# signal_processing_module.net
KiCad netlist of a schematic drawn in EAGLE
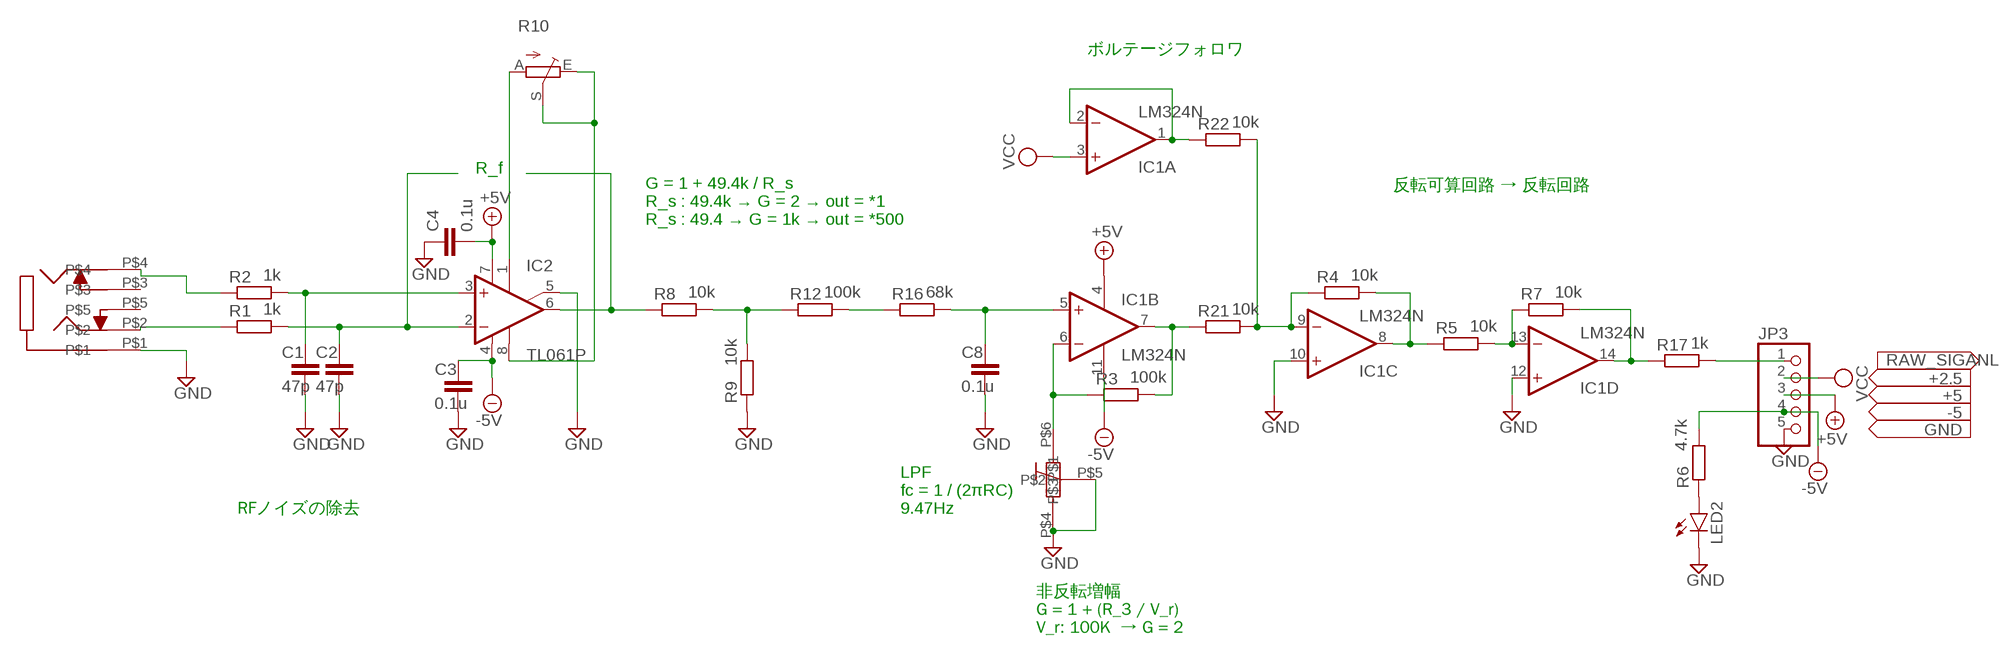
[diagram p0: schematic, sheet 1]

(export (version "E")
  (design (tool "Eeschema 10.0.6"))
  (components
    (comp (ref "C1")
      (value "47p")
      (footprint "eagle-import:C025-024X044")
      (libsource (lib "eagle-import") (part "C-EU025-024X044"))
    )
    (comp (ref "C2")
      (value "47p")
      (footprint "eagle-import:C025-024X044")
      (libsource (lib "eagle-import") (part "C-EU025-024X044"))
    )
    (comp (ref "C3")
      (value "0.1u")
      (footprint "eagle-import:C025-024X044")
      (libsource (lib "eagle-import") (part "C-EU025-024X044"))
    )
    (comp (ref "C4")
      (value "0.1u")
      (footprint "eagle-import:C025-024X044")
      (libsource (lib "eagle-import") (part "C-EU025-024X044"))
    )
    (comp (ref "C8")
      (value "0.1u")
      (footprint "eagle-import:C025-024X044")
      (libsource (lib "eagle-import") (part "C-EU025-024X044"))
    )
    (comp (ref "IC1")
      (value "LM324N")
      (footprint "eagle-import:DIL14")
      (libsource (lib "eagle-import") (part "LM324N"))
    )
    (comp (ref "IC2")
      (value "TL061P")
      (footprint "eagle-import:DIL08")
      (libsource (lib "eagle-import") (part "TL061P"))
    )
    (comp (ref "JP3")
      (value "PINHD-1X5")
      (footprint "eagle-import:1X05")
      (libsource (lib "eagle-import") (part "PINHD-1X5"))
    )
    (comp (ref "LED2")
      (value "LED3MM")
      (footprint "eagle-import:LED3MM")
      (libsource (lib "eagle-import") (part "LED3MM"))
    )
    (comp (ref "R1")
      (value "1k")
      (footprint "eagle-import:0204_7")
      (libsource (lib "eagle-import") (part "R-EU_0204/7"))
    )
    (comp (ref "R2")
      (value "1k")
      (footprint "eagle-import:0204_7")
      (libsource (lib "eagle-import") (part "R-EU_0204/7"))
    )
    (comp (ref "R3")
      (value "100k")
      (footprint "eagle-import:0204_7")
      (libsource (lib "eagle-import") (part "R-EU_0204/7"))
    )
    (comp (ref "R4")
      (value "10k")
      (footprint "eagle-import:0204_7")
      (libsource (lib "eagle-import") (part "R-EU_0204/7"))
    )
    (comp (ref "R5")
      (value "10k")
      (footprint "eagle-import:0204_7")
      (libsource (lib "eagle-import") (part "R-EU_0204/7"))
    )
    (comp (ref "R6")
      (value "4.7k")
      (footprint "eagle-import:0204_7")
      (libsource (lib "eagle-import") (part "R-EU_0204/7"))
    )
    (comp (ref "R7")
      (value "10k")
      (footprint "eagle-import:0204_7")
      (libsource (lib "eagle-import") (part "R-EU_0204/7"))
    )
    (comp (ref "R8")
      (value "10k")
      (footprint "eagle-import:0204_7")
      (libsource (lib "eagle-import") (part "R-EU_0204/7"))
    )
    (comp (ref "R9")
      (value "10k")
      (footprint "eagle-import:0204_7")
      (libsource (lib "eagle-import") (part "R-EU_0204/7"))
    )
    (comp (ref "R10")
      (value "TRIM_EU-RS3")
      (footprint "eagle-import:RS3")
      (libsource (lib "eagle-import") (part "TRIM_EU-RS3"))
    )
    (comp (ref "R12")
      (value "100k")
      (footprint "eagle-import:0204_7")
      (libsource (lib "eagle-import") (part "R-EU_0204/7"))
    )
    (comp (ref "R16")
      (value "68k")
      (footprint "eagle-import:0204_7")
      (libsource (lib "eagle-import") (part "R-EU_0204/7"))
    )
    (comp (ref "R17")
      (value "1k")
      (footprint "eagle-import:0204_7")
      (libsource (lib "eagle-import") (part "R-EU_0204/7"))
    )
    (comp (ref "R21")
      (value "10k")
      (footprint "eagle-import:0204_7")
      (libsource (lib "eagle-import") (part "R-EU_0204/7"))
    )
    (comp (ref "R22")
      (value "10k")
      (footprint "eagle-import:0204_7")
      (libsource (lib "eagle-import") (part "R-EU_0204/7"))
    )
    (comp (ref "U$2")
      (value "MJ-354W-SG")
      (footprint "eagle-import:MJ-354W-SG")
      (libsource (lib "eagle-import") (part "MJ-354W-SG"))
    )
    (comp (ref "U$3")
      (value "VR_2CH")
      (footprint "eagle-import:2CH_VR")
      (libsource (lib "eagle-import") (part "VR_2CH"))
    )
  )
  (nets
    (net (code "1") (name "+5V") (class "Default")
      (node (ref "C4") (pin "2") (pinfunction "2_2") (pintype "passive"))
      (node (ref "IC1") (pin "4") (pinfunction "V+_4") (pintype "power_in"))
      (node (ref "IC2") (pin "7") (pinfunction "V+_7") (pintype "power_in"))
      (node (ref "JP3") (pin "3") (pinfunction "3_3") (pintype "passive"))
    )
    (net (code "2") (name "-5V") (class "Default")
      (node (ref "C3") (pin "1") (pinfunction "1_1") (pintype "passive"))
      (node (ref "IC1") (pin "11") (pinfunction "V-_11") (pintype "power_in"))
      (node (ref "IC2") (pin "4") (pinfunction "V-_4") (pintype "power_in"))
      (node (ref "JP3") (pin "4") (pinfunction "4_4") (pintype "passive"))
      (node (ref "R6") (pin "2") (pinfunction "2_2") (pintype "passive"))
    )
    (net (code "3") (name "GND") (class "Default")
      (node (ref "C1") (pin "2") (pinfunction "2_2") (pintype "passive"))
      (node (ref "C2") (pin "2") (pinfunction "2_2") (pintype "passive"))
      (node (ref "C3") (pin "2") (pinfunction "2_2") (pintype "passive"))
      (node (ref "C4") (pin "1") (pinfunction "1_1") (pintype "passive"))
      (node (ref "C8") (pin "2") (pinfunction "2_2") (pintype "passive"))
      (node (ref "IC1") (pin "10") (pinfunction "+IN_10") (pintype "input"))
      (node (ref "IC1") (pin "12") (pinfunction "+IN_12") (pintype "input"))
      (node (ref "IC2") (pin "5") (pinfunction "ON2_5") (pintype "passive"))
      (node (ref "JP3") (pin "5") (pinfunction "5_5") (pintype "passive"))
      (node (ref "LED2") (pin "K") (pinfunction "C_K") (pintype "passive"))
      (node (ref "R9") (pin "1") (pinfunction "1_1") (pintype "passive"))
      (node (ref "U$2") (pin "P$1") (pinfunction "P$1_P$1") (pintype "bidirectional"))
      (node (ref "U$3") (pin "P$4") (pinfunction "P$1_P$4") (pintype "bidirectional"))
      (node (ref "U$3") (pin "P$5") (pinfunction "P$2_P$5") (pintype "bidirectional"))
    )
    (net (code "4") (name "Net-(IC1A--IN)") (class "Default")
      (node (ref "IC1") (pin "1") (pinfunction "OUT_1") (pintype "output"))
      (node (ref "IC1") (pin "2") (pinfunction "-IN_2") (pintype "input"))
      (node (ref "R22") (pin "1") (pinfunction "1_1") (pintype "passive"))
    )
    (net (code "5") (name "Net-(IC1B-+IN)") (class "Default")
      (node (ref "C8") (pin "1") (pinfunction "1_1") (pintype "passive"))
      (node (ref "IC1") (pin "5") (pinfunction "+IN_5") (pintype "input"))
      (node (ref "R16") (pin "2") (pinfunction "2_2") (pintype "passive"))
    )
    (net (code "6") (name "Net-(IC1B--IN)") (class "Default")
      (node (ref "IC1") (pin "6") (pinfunction "-IN_6") (pintype "input"))
      (node (ref "R3") (pin "1") (pinfunction "1_1") (pintype "passive"))
      (node (ref "U$3") (pin "P$6") (pinfunction "P$3_P$6") (pintype "bidirectional"))
    )
    (net (code "7") (name "Net-(IC1B-OUT)") (class "Default")
      (node (ref "IC1") (pin "7") (pinfunction "OUT_7") (pintype "output"))
      (node (ref "R21") (pin "1") (pinfunction "1_1") (pintype "passive"))
      (node (ref "R3") (pin "2") (pinfunction "2_2") (pintype "passive"))
    )
    (net (code "8") (name "Net-(IC1C--IN)") (class "Default")
      (node (ref "IC1") (pin "9") (pinfunction "-IN_9") (pintype "input"))
      (node (ref "R21") (pin "2") (pinfunction "2_2") (pintype "passive"))
      (node (ref "R22") (pin "2") (pinfunction "2_2") (pintype "passive"))
      (node (ref "R4") (pin "1") (pinfunction "1_1") (pintype "passive"))
    )
    (net (code "9") (name "Net-(IC1C-OUT)") (class "Default")
      (node (ref "IC1") (pin "8") (pinfunction "OUT_8") (pintype "output"))
      (node (ref "R4") (pin "2") (pinfunction "2_2") (pintype "passive"))
      (node (ref "R5") (pin "1") (pinfunction "1_1") (pintype "passive"))
    )
    (net (code "10") (name "Net-(IC1D--IN)") (class "Default")
      (node (ref "IC1") (pin "13") (pinfunction "-IN_13") (pintype "input"))
      (node (ref "R5") (pin "2") (pinfunction "2_2") (pintype "passive"))
      (node (ref "R7") (pin "1") (pinfunction "1_1") (pintype "passive"))
    )
    (net (code "11") (name "Net-(IC1D-OUT)") (class "Default")
      (node (ref "IC1") (pin "14") (pinfunction "OUT_14") (pintype "output"))
      (node (ref "R17") (pin "1") (pinfunction "1_1") (pintype "passive"))
      (node (ref "R7") (pin "2") (pinfunction "2_2") (pintype "passive"))
    )
    (net (code "12") (name "Net-(IC2-+IN)") (class "Default")
      (node (ref "C1") (pin "1") (pinfunction "1_1") (pintype "passive"))
      (node (ref "IC2") (pin "3") (pinfunction "+IN_3") (pintype "input"))
      (node (ref "R2") (pin "2") (pinfunction "2_2") (pintype "passive"))
    )
    (net (code "13") (name "Net-(IC2--IN)") (class "Default")
      (node (ref "C2") (pin "1") (pinfunction "1_1") (pintype "passive"))
      (node (ref "IC2") (pin "2") (pinfunction "-IN_2") (pintype "input"))
      (node (ref "R1") (pin "2") (pinfunction "2_2") (pintype "passive"))
    )
    (net (code "14") (name "Net-(IC2-ON1)") (class "Default")
      (node (ref "IC2") (pin "1") (pinfunction "ON1_1") (pintype "passive"))
      (node (ref "R10") (pin "A") (pinfunction "A_A") (pintype "passive"))
    )
    (net (code "15") (name "Net-(IC2-OPT)") (class "Default")
      (node (ref "IC2") (pin "8") (pinfunction "OPT_8") (pintype "passive"))
      (node (ref "R10") (pin "E") (pinfunction "E_E") (pintype "passive"))
      (node (ref "R10") (pin "S") (pinfunction "S_S") (pintype "passive"))
    )
    (net (code "16") (name "Net-(IC2-OUT)") (class "Default")
      (node (ref "IC2") (pin "6") (pinfunction "OUT_6") (pintype "output"))
      (node (ref "R8") (pin "1") (pinfunction "1_1") (pintype "passive"))
    )
    (net (code "17") (name "Net-(JP3-Pad1)") (class "Default")
      (node (ref "JP3") (pin "1") (pinfunction "1_1") (pintype "passive"))
      (node (ref "R17") (pin "2") (pinfunction "2_2") (pintype "passive"))
    )
    (net (code "18") (name "Net-(LED2-PadA)") (class "Default")
      (node (ref "LED2") (pin "A") (pinfunction "A_A") (pintype "passive"))
      (node (ref "R6") (pin "1") (pinfunction "1_1") (pintype "passive"))
    )
    (net (code "19") (name "Net-(R1-Pad1)") (class "Default")
      (node (ref "R1") (pin "1") (pinfunction "1_1") (pintype "passive"))
      (node (ref "U$2") (pin "P$2") (pinfunction "P$2_P$2") (pintype "bidirectional"))
    )
    (net (code "20") (name "Net-(R2-Pad1)") (class "Default")
      (node (ref "R2") (pin "1") (pinfunction "1_1") (pintype "passive"))
      (node (ref "U$2") (pin "P$4") (pinfunction "P$4_P$4") (pintype "bidirectional"))
    )
    (net (code "21") (name "Net-(R12-Pad1)") (class "Default")
      (node (ref "R12") (pin "1") (pinfunction "1_1") (pintype "passive"))
      (node (ref "R8") (pin "2") (pinfunction "2_2") (pintype "passive"))
      (node (ref "R9") (pin "2") (pinfunction "2_2") (pintype "passive"))
    )
    (net (code "22") (name "Net-(R12-Pad2)") (class "Default")
      (node (ref "R12") (pin "2") (pinfunction "2_2") (pintype "passive"))
      (node (ref "R16") (pin "1") (pinfunction "1_1") (pintype "passive"))
    )
    (net (code "23") (name "VCC") (class "Default")
      (node (ref "IC1") (pin "3") (pinfunction "+IN_3") (pintype "input"))
      (node (ref "JP3") (pin "2") (pinfunction "2_2") (pintype "passive"))
    )
    (net (code "24") (name "unconnected-(U$2-PadP$3)") (class "Default")
      (node (ref "U$2") (pin "P$3") (pinfunction "P$3_P$3") (pintype "bidirectional"))
    )
    (net (code "25") (name "unconnected-(U$2-PadP$5)") (class "Default")
      (node (ref "U$2") (pin "P$5") (pinfunction "P$5_P$5") (pintype "bidirectional"))
    )
  )
)
